# playa.net
KiCad netlist of a schematic drawn in EAGLE
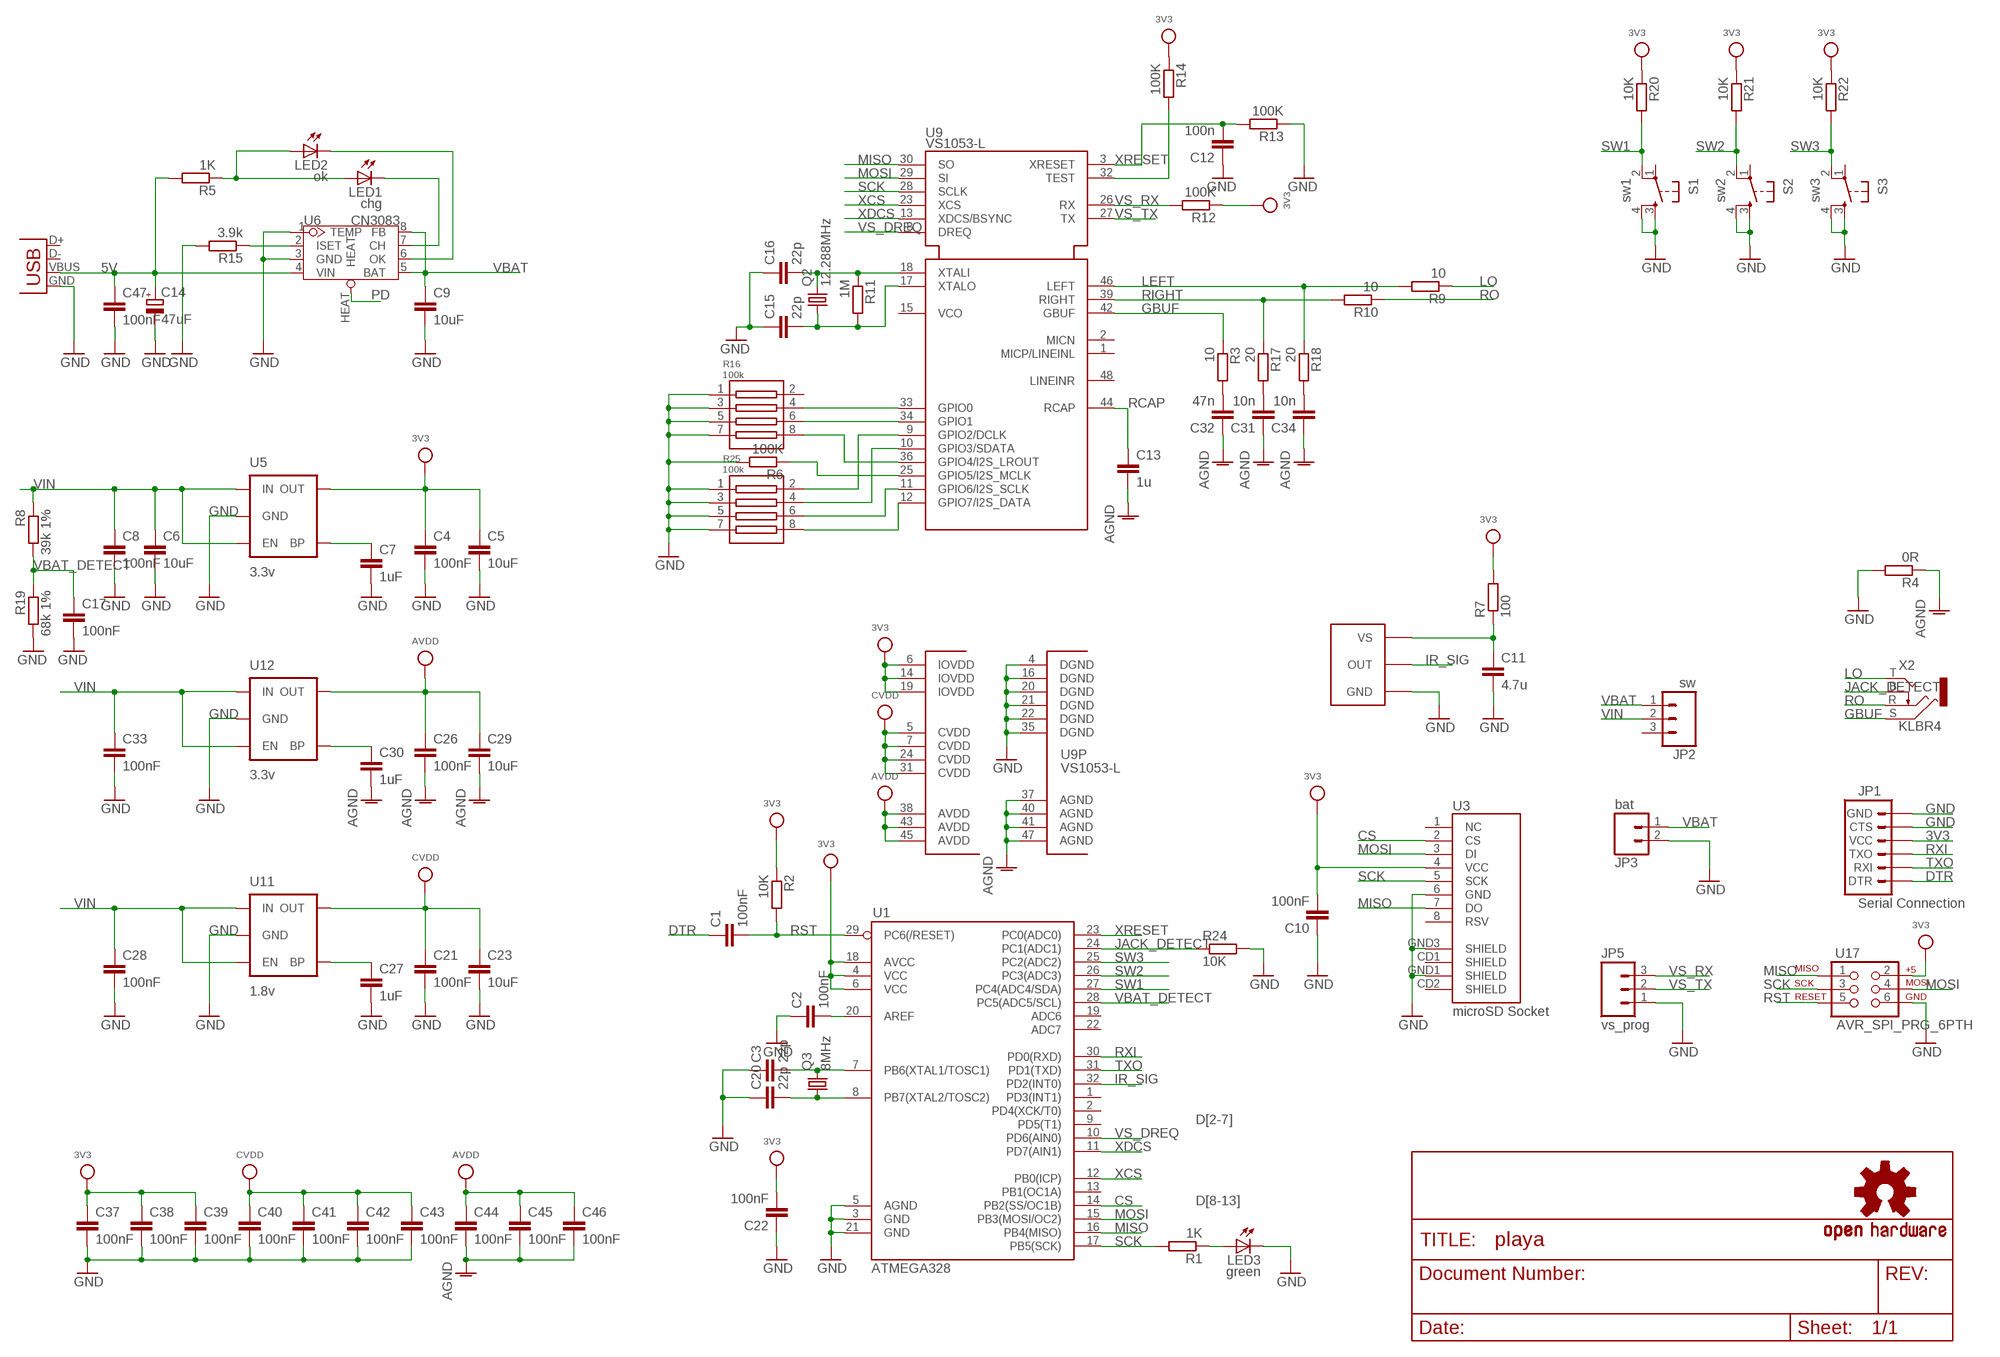
[diagram p0: schematic, sheet 1]

(export (version "E")
  (design (tool "Eeschema 10.0.6"))
  (components
    (comp (ref "C1")
      (value "100nF")
      (footprint "eagle-import:C0805")
      (libsource (lib "eagle-import") (part "C-EUC0805"))
    )
    (comp (ref "C2")
      (value "100nF")
      (footprint "eagle-import:C0805")
      (libsource (lib "eagle-import") (part "C-EUC0805"))
    )
    (comp (ref "C3")
      (value "22p")
      (footprint "eagle-import:C0805")
      (libsource (lib "eagle-import") (part "C-EUC0805"))
    )
    (comp (ref "C4")
      (value "100nF")
      (footprint "eagle-import:C0805")
      (libsource (lib "eagle-import") (part "C-EUC0805"))
    )
    (comp (ref "C5")
      (value "10uF")
      (footprint "eagle-import:C1206")
      (libsource (lib "eagle-import") (part "C-EUC1206"))
    )
    (comp (ref "C6")
      (value "10uF")
      (footprint "eagle-import:C1206")
      (libsource (lib "eagle-import") (part "C-EUC1206"))
    )
    (comp (ref "C7")
      (value "1uF")
      (footprint "eagle-import:C0805")
      (libsource (lib "eagle-import") (part "C-EUC0805"))
    )
    (comp (ref "C8")
      (value "100nF")
      (footprint "eagle-import:C0805")
      (libsource (lib "eagle-import") (part "C-EUC0805"))
    )
    (comp (ref "C9")
      (value "10uF")
      (footprint "eagle-import:C1206")
      (libsource (lib "eagle-import") (part "C-EUC1206"))
    )
    (comp (ref "C10")
      (value "100nF")
      (footprint "eagle-import:C0805")
      (libsource (lib "eagle-import") (part "C-EUC0805"))
    )
    (comp (ref "C11")
      (value "4.7u")
      (footprint "eagle-import:C1206")
      (libsource (lib "eagle-import") (part "C-EUC1206"))
    )
    (comp (ref "C12")
      (value "100n")
      (footprint "eagle-import:C0805")
      (libsource (lib "eagle-import") (part "C-EUC0805"))
    )
    (comp (ref "C13")
      (value "1u")
      (footprint "eagle-import:C0805")
      (libsource (lib "eagle-import") (part "C-EUC0805"))
    )
    (comp (ref "C14")
      (value "47uF")
      (footprint "eagle-import:CT7343")
      (libsource (lib "eagle-import") (part "CPOL-EUCT7343"))
    )
    (comp (ref "C15")
      (value "22p")
      (footprint "eagle-import:C0805")
      (libsource (lib "eagle-import") (part "C-EUC0805"))
    )
    (comp (ref "C16")
      (value "22p")
      (footprint "eagle-import:C0805")
      (libsource (lib "eagle-import") (part "C-EUC0805"))
    )
    (comp (ref "C17")
      (value "100nF")
      (footprint "eagle-import:C0805")
      (libsource (lib "eagle-import") (part "C-EUC0805"))
    )
    (comp (ref "C20")
      (value "22p")
      (footprint "eagle-import:C0805")
      (libsource (lib "eagle-import") (part "C-EUC0805"))
    )
    (comp (ref "C21")
      (value "100nF")
      (footprint "eagle-import:C0805")
      (libsource (lib "eagle-import") (part "C-EUC0805"))
    )
    (comp (ref "C22")
      (value "100nF")
      (footprint "eagle-import:C0805")
      (libsource (lib "eagle-import") (part "C-EUC0805"))
    )
    (comp (ref "C23")
      (value "10uF")
      (footprint "eagle-import:C1206")
      (libsource (lib "eagle-import") (part "C-EUC1206"))
    )
    (comp (ref "C26")
      (value "100nF")
      (footprint "eagle-import:C0805")
      (libsource (lib "eagle-import") (part "C-EUC0805"))
    )
    (comp (ref "C27")
      (value "1uF")
      (footprint "eagle-import:C0805")
      (libsource (lib "eagle-import") (part "C-EUC0805"))
    )
    (comp (ref "C28")
      (value "100nF")
      (footprint "eagle-import:C0805")
      (libsource (lib "eagle-import") (part "C-EUC0805"))
    )
    (comp (ref "C29")
      (value "10uF")
      (footprint "eagle-import:C1206")
      (libsource (lib "eagle-import") (part "C-EUC1206"))
    )
    (comp (ref "C30")
      (value "1uF")
      (footprint "eagle-import:C0805")
      (libsource (lib "eagle-import") (part "C-EUC0805"))
    )
    (comp (ref "C31")
      (value "10n")
      (footprint "eagle-import:C0805")
      (libsource (lib "eagle-import") (part "C-EUC0805"))
    )
    (comp (ref "C32")
      (value "47n")
      (footprint "eagle-import:C0805")
      (libsource (lib "eagle-import") (part "C-EUC0805"))
    )
    (comp (ref "C33")
      (value "100nF")
      (footprint "eagle-import:C0805")
      (libsource (lib "eagle-import") (part "C-EUC0805"))
    )
    (comp (ref "C34")
      (value "10n")
      (footprint "eagle-import:C0805")
      (libsource (lib "eagle-import") (part "C-EUC0805"))
    )
    (comp (ref "C37")
      (value "100nF")
      (footprint "eagle-import:C0805")
      (libsource (lib "eagle-import") (part "C-EUC0805"))
    )
    (comp (ref "C38")
      (value "100nF")
      (footprint "eagle-import:C0805")
      (libsource (lib "eagle-import") (part "C-EUC0805"))
    )
    (comp (ref "C39")
      (value "100nF")
      (footprint "eagle-import:C0805")
      (libsource (lib "eagle-import") (part "C-EUC0805"))
    )
    (comp (ref "C40")
      (value "100nF")
      (footprint "eagle-import:C0805")
      (libsource (lib "eagle-import") (part "C-EUC0805"))
    )
    (comp (ref "C41")
      (value "100nF")
      (footprint "eagle-import:C0805")
      (libsource (lib "eagle-import") (part "C-EUC0805"))
    )
    (comp (ref "C42")
      (value "100nF")
      (footprint "eagle-import:C0805")
      (libsource (lib "eagle-import") (part "C-EUC0805"))
    )
    (comp (ref "C43")
      (value "100nF")
      (footprint "eagle-import:C0805")
      (libsource (lib "eagle-import") (part "C-EUC0805"))
    )
    (comp (ref "C44")
      (value "100nF")
      (footprint "eagle-import:C0805")
      (libsource (lib "eagle-import") (part "C-EUC0805"))
    )
    (comp (ref "C45")
      (value "100nF")
      (footprint "eagle-import:C0805")
      (libsource (lib "eagle-import") (part "C-EUC0805"))
    )
    (comp (ref "C46")
      (value "100nF")
      (footprint "eagle-import:C0805")
      (libsource (lib "eagle-import") (part "C-EUC0805"))
    )
    (comp (ref "C47")
      (value "100nF")
      (footprint "eagle-import:C0805")
      (libsource (lib "eagle-import") (part "C-EUC0805"))
    )
    (comp (ref "JP1")
      (value "Serial Connection")
      (footprint "eagle-import:1X06")
      (libsource (lib "eagle-import") (part "ARDUINO_SERIAL_PROGRAMPTH"))
    )
    (comp (ref "JP2")
      (value "sw")
      (footprint "eagle-import:1X03")
      (libsource (lib "eagle-import") (part "M03PTH"))
    )
    (comp (ref "JP3")
      (value "bat")
      (footprint "eagle-import:1X02")
      (libsource (lib "eagle-import") (part "M02PTH"))
    )
    (comp (ref "JP5")
      (value "vs_prog")
      (footprint "eagle-import:1X03")
      (libsource (lib "eagle-import") (part "M03PTH"))
    )
    (comp (ref "LED1")
      (value "chg")
      (footprint "eagle-import:CHIP-LED0805")
      (libsource (lib "eagle-import") (part "LEDCHIP-LED0805"))
    )
    (comp (ref "LED2")
      (value "ok")
      (footprint "eagle-import:CHIP-LED0805")
      (libsource (lib "eagle-import") (part "LEDCHIP-LED0805"))
    )
    (comp (ref "LED3")
      (value "green")
      (footprint "eagle-import:CHIP-LED0805")
      (libsource (lib "eagle-import") (part "LEDCHIP-LED0805"))
    )
    (comp (ref "Q2")
      (value "12.288MHz")
      (footprint "eagle-import:CRYSTAL_5X3.2")
      (libsource (lib "eagle-import") (part "CRYTAL"))
    )
    (comp (ref "Q3")
      (value "8MHz")
      (footprint "eagle-import:CRYSTAL_5X3.2")
      (libsource (lib "eagle-import") (part "CRYTAL"))
    )
    (comp (ref "R1")
      (value "1K")
      (footprint "eagle-import:R0805W")
      (libsource (lib "eagle-import") (part "R-EU_R0805W"))
    )
    (comp (ref "R2")
      (value "10K")
      (footprint "eagle-import:R0805W")
      (libsource (lib "eagle-import") (part "R-EU_R0805W"))
    )
    (comp (ref "R3")
      (value "10")
      (footprint "eagle-import:R0805W")
      (libsource (lib "eagle-import") (part "R-EU_R0805W"))
    )
    (comp (ref "R4")
      (value "0R")
      (footprint "eagle-import:R0805W")
      (libsource (lib "eagle-import") (part "R-EU_R0805W"))
    )
    (comp (ref "R5")
      (value "1K")
      (footprint "eagle-import:R0805W")
      (libsource (lib "eagle-import") (part "R-EU_R0805W"))
    )
    (comp (ref "R6")
      (value "100K")
      (footprint "eagle-import:R0805W")
      (libsource (lib "eagle-import") (part "R-EU_R0805W"))
    )
    (comp (ref "R7")
      (value "100")
      (footprint "eagle-import:R0805W")
      (libsource (lib "eagle-import") (part "R-EU_R0805W"))
    )
    (comp (ref "R8")
      (value "39k 1%")
      (footprint "eagle-import:R0805W")
      (libsource (lib "eagle-import") (part "R-EU_R0805W"))
    )
    (comp (ref "R9")
      (value "10")
      (footprint "eagle-import:R0805W")
      (libsource (lib "eagle-import") (part "R-EU_R0805W"))
    )
    (comp (ref "R10")
      (value "10")
      (footprint "eagle-import:R0805W")
      (libsource (lib "eagle-import") (part "R-EU_R0805W"))
    )
    (comp (ref "R11")
      (value "1M")
      (footprint "eagle-import:R0805W")
      (libsource (lib "eagle-import") (part "R-EU_R0805W"))
    )
    (comp (ref "R12")
      (value "100K")
      (footprint "eagle-import:R0805W")
      (libsource (lib "eagle-import") (part "R-EU_R0805W"))
    )
    (comp (ref "R13")
      (value "100K")
      (footprint "eagle-import:R0805W")
      (libsource (lib "eagle-import") (part "R-EU_R0805W"))
    )
    (comp (ref "R14")
      (value "100K")
      (footprint "eagle-import:R0805W")
      (libsource (lib "eagle-import") (part "R-EU_R0805W"))
    )
    (comp (ref "R15")
      (value "3.9k")
      (footprint "eagle-import:R0805W")
      (libsource (lib "eagle-import") (part "R-EU_R0805W"))
    )
    (comp (ref "R16")
      (value "100k")
      (footprint "eagle-import:RAS_ARR_1206")
      (libsource (lib "eagle-import") (part "RES_ARR_1206"))
    )
    (comp (ref "R17")
      (value "20")
      (footprint "eagle-import:R0805W")
      (libsource (lib "eagle-import") (part "R-EU_R0805W"))
    )
    (comp (ref "R18")
      (value "20")
      (footprint "eagle-import:R0805W")
      (libsource (lib "eagle-import") (part "R-EU_R0805W"))
    )
    (comp (ref "R19")
      (value "68k 1%")
      (footprint "eagle-import:R0805W")
      (libsource (lib "eagle-import") (part "R-EU_R0805W"))
    )
    (comp (ref "R20")
      (value "10K")
      (footprint "eagle-import:R0805W")
      (libsource (lib "eagle-import") (part "R-EU_R0805W"))
    )
    (comp (ref "R21")
      (value "10K")
      (footprint "eagle-import:R0805W")
      (libsource (lib "eagle-import") (part "R-EU_R0805W"))
    )
    (comp (ref "R22")
      (value "10K")
      (footprint "eagle-import:R0805W")
      (libsource (lib "eagle-import") (part "R-EU_R0805W"))
    )
    (comp (ref "R24")
      (value "10K")
      (footprint "eagle-import:R0805W")
      (libsource (lib "eagle-import") (part "R-EU_R0805W"))
    )
    (comp (ref "R25")
      (value "100k")
      (footprint "eagle-import:RAS_ARR_1206")
      (libsource (lib "eagle-import") (part "RES_ARR_1206"))
    )
    (comp (ref "S1")
      (value "sw1")
      (footprint "eagle-import:TACTILE_SWITCH_SMD")
      (libsource (lib "eagle-import") (part "TAC_SWITCHSMD"))
    )
    (comp (ref "S2")
      (value "sw2")
      (footprint "eagle-import:TACTILE_SWITCH_SMD")
      (libsource (lib "eagle-import") (part "TAC_SWITCHSMD"))
    )
    (comp (ref "S3")
      (value "sw3")
      (footprint "eagle-import:TACTILE_SWITCH_SMD")
      (libsource (lib "eagle-import") (part "TAC_SWITCHSMD"))
    )
    (comp (ref "U$3")
      (value "TSOP312X")
      (footprint "eagle-import:TSOP312X")
      (libsource (lib "eagle-import") (part "TSOP312X"))
    )
    (comp (ref "U$5")
      (value "OSHW-LOGOM")
      (footprint "eagle-import:OSHW-LOGO-M")
      (libsource (lib "eagle-import") (part "OSHW-LOGOM"))
    )
    (comp (ref "U1")
      (value "ATMEGA328")
      (footprint "eagle-import:TQFP32-08")
      (libsource (lib "eagle-import") (part "ATMEGA168"))
    )
    (comp (ref "U3")
      (value "microSD Socket")
      (footprint "eagle-import:MICRO-SD-SOCKET-PP")
      (libsource (lib "eagle-import") (part "USD-SOCKETNEW"))
    )
    (comp (ref "U5")
      (value "3.3v")
      (footprint "eagle-import:SOT23-5")
      (libsource (lib "eagle-import") (part "V_REG_LDOSMD"))
    )
    (comp (ref "U6")
      (value "CN3083")
      (footprint "eagle-import:SOP8-W_-HEAT")
      (libsource (lib "eagle-import") (part "CN3083"))
    )
    (comp (ref "U9")
      (value "VS1053-L")
      (footprint "eagle-import:LQFP48")
      (libsource (lib "eagle-import") (part "VS1053-L"))
    )
    (comp (ref "U11")
      (value "1.8v")
      (footprint "eagle-import:SOT23-5")
      (libsource (lib "eagle-import") (part "V_REG_LDOSMD"))
    )
    (comp (ref "U12")
      (value "3.3v")
      (footprint "eagle-import:SOT23-5")
      (libsource (lib "eagle-import") (part "V_REG_LDOSMD"))
    )
    (comp (ref "U17")
      (value "AVR_SPI_PRG_6PTH")
      (footprint "eagle-import:2X3")
      (libsource (lib "eagle-import") (part "AVR_SPI_PRG_6PTH"))
    )
    (comp (ref "X1")
      (value "USBSMD")
      (footprint "eagle-import:USB-MINIB")
      (libsource (lib "eagle-import") (part "USBSMD"))
    )
    (comp (ref "X2")
      (value "KLBR4")
      (footprint "eagle-import:KLBR4")
      (fields (field (name "MPN") "KLBR 4"))
      (libsource (lib "eagle-import") (part "KLBR4"))
    )
  )
  (nets
    (net (code "1") (name "/5V") (class "Default")
      (node (ref "C14") (pin "+") (pinfunction "+_+") (pintype "passive"))
      (node (ref "C47") (pin "1") (pinfunction "1_1") (pintype "passive"))
      (node (ref "R5") (pin "2") (pinfunction "2_2") (pintype "passive"))
      (node (ref "U6") (pin "4") (pinfunction "VIN_4") (pintype "bidirectional"))
      (node (ref "X1") (pin "VBUS") (pinfunction "VBUS_VBUS") (pintype "bidirectional"))
    )
    (net (code "2") (name "/CS") (class "Default")
      (node (ref "U1") (pin "14") (pinfunction "PB2(SS/OC1B)_14") (pintype "bidirectional"))
      (node (ref "U3") (pin "2") (pinfunction "CS_2") (pintype "bidirectional"))
    )
    (net (code "3") (name "/DTR") (class "Default")
      (node (ref "C1") (pin "1") (pinfunction "1_1") (pintype "passive"))
      (node (ref "JP1") (pin "1") (pinfunction "DTR_1") (pintype "passive"))
    )
    (net (code "4") (name "/GBUF") (class "Default")
      (node (ref "R3") (pin "1") (pinfunction "1_1") (pintype "passive"))
      (node (ref "U9") (pin "42") (pinfunction "GBUF_42") (pintype "output"))
      (node (ref "X2") (pin "S") (pinfunction "S_S") (pintype "passive"))
    )
    (net (code "5") (name "/IR_SIG") (class "Default")
      (node (ref "U$3") (pin "3") (pinfunction "OUT_3") (pintype "bidirectional"))
      (node (ref "U1") (pin "32") (pinfunction "PD2(INT0)_32") (pintype "bidirectional"))
    )
    (net (code "6") (name "/JACK_DETECT") (class "Default")
      (node (ref "R24") (pin "1") (pinfunction "1_1") (pintype "passive"))
      (node (ref "U1") (pin "24") (pinfunction "PC1(ADC1)_24") (pintype "bidirectional"))
      (node (ref "X2") (pin "B") (pinfunction "B_B") (pintype "passive"))
    )
    (net (code "7") (name "/LEFT") (class "Default")
      (node (ref "R18") (pin "1") (pinfunction "1_1") (pintype "passive"))
      (node (ref "R9") (pin "2") (pinfunction "2_2") (pintype "passive"))
      (node (ref "U9") (pin "46") (pinfunction "LEFT_46") (pintype "output"))
    )
    (net (code "8") (name "/LO") (class "Default")
      (node (ref "R9") (pin "1") (pinfunction "1_1") (pintype "passive"))
      (node (ref "X2") (pin "T") (pinfunction "T_T") (pintype "passive"))
    )
    (net (code "9") (name "/MISO") (class "Default")
      (node (ref "U1") (pin "16") (pinfunction "PB4(MISO)_16") (pintype "bidirectional"))
      (node (ref "U17") (pin "1") (pinfunction "1_1") (pintype "passive"))
      (node (ref "U3") (pin "7") (pinfunction "DO_7") (pintype "bidirectional"))
      (node (ref "U9") (pin "30") (pinfunction "SO_30") (pintype "output"))
    )
    (net (code "10") (name "/MOSI") (class "Default")
      (node (ref "U1") (pin "15") (pinfunction "PB3(MOSI/OC2)_15") (pintype "bidirectional"))
      (node (ref "U17") (pin "4") (pinfunction "4_4") (pintype "passive"))
      (node (ref "U3") (pin "3") (pinfunction "DI_3") (pintype "bidirectional"))
      (node (ref "U9") (pin "29") (pinfunction "SI_29") (pintype "input"))
    )
    (net (code "11") (name "/PD") (class "Default")
      (node (ref "U6") (pin "HEAT") (pinfunction "HEAT_HEAT") (pintype "bidirectional"))
    )
    (net (code "12") (name "/RCAP") (class "Default")
      (node (ref "C13") (pin "1") (pinfunction "1_1") (pintype "passive"))
      (node (ref "U9") (pin "44") (pinfunction "RCAP_44") (pintype "bidirectional"))
    )
    (net (code "13") (name "/RIGHT") (class "Default")
      (node (ref "R10") (pin "2") (pinfunction "2_2") (pintype "passive"))
      (node (ref "R17") (pin "1") (pinfunction "1_1") (pintype "passive"))
      (node (ref "U9") (pin "39") (pinfunction "RIGHT_39") (pintype "output"))
    )
    (net (code "14") (name "/RO") (class "Default")
      (node (ref "R10") (pin "1") (pinfunction "1_1") (pintype "passive"))
      (node (ref "X2") (pin "R") (pinfunction "R_R") (pintype "passive"))
    )
    (net (code "15") (name "/RST") (class "Default")
      (node (ref "C1") (pin "2") (pinfunction "2_2") (pintype "passive"))
      (node (ref "R2") (pin "2") (pinfunction "2_2") (pintype "passive"))
      (node (ref "U1") (pin "29") (pinfunction "PC6(/RESET)_29") (pintype "bidirectional"))
      (node (ref "U17") (pin "5") (pinfunction "5_5") (pintype "passive"))
    )
    (net (code "16") (name "/RXI") (class "Default")
      (node (ref "JP1") (pin "3") (pinfunction "TXO_3") (pintype "passive"))
      (node (ref "U1") (pin "30") (pinfunction "PD0(RXD)_30") (pintype "bidirectional"))
    )
    (net (code "17") (name "/SCK") (class "Default")
      (node (ref "R1") (pin "2") (pinfunction "2_2") (pintype "passive"))
      (node (ref "U1") (pin "17") (pinfunction "PB5(SCK)_17") (pintype "bidirectional"))
      (node (ref "U17") (pin "3") (pinfunction "3_3") (pintype "passive"))
      (node (ref "U3") (pin "5") (pinfunction "SCK_5") (pintype "bidirectional"))
      (node (ref "U9") (pin "28") (pinfunction "SCLK_28") (pintype "input"))
    )
    (net (code "18") (name "/SW1") (class "Default")
      (node (ref "R20") (pin "2") (pinfunction "2_2") (pintype "passive"))
      (node (ref "S1") (pin "2") (pinfunction "2_2") (pintype "passive"))
      (node (ref "U1") (pin "27") (pinfunction "PC4(ADC4/SDA)_27") (pintype "bidirectional"))
    )
    (net (code "19") (name "/SW2") (class "Default")
      (node (ref "R21") (pin "2") (pinfunction "2_2") (pintype "passive"))
      (node (ref "S2") (pin "2") (pinfunction "2_2") (pintype "passive"))
      (node (ref "U1") (pin "26") (pinfunction "PC3(ADC3)_26") (pintype "bidirectional"))
    )
    (net (code "20") (name "/SW3") (class "Default")
      (node (ref "R22") (pin "2") (pinfunction "2_2") (pintype "passive"))
      (node (ref "S3") (pin "2") (pinfunction "2_2") (pintype "passive"))
      (node (ref "U1") (pin "25") (pinfunction "PC2(ADC2)_25") (pintype "bidirectional"))
    )
    (net (code "21") (name "/TXO") (class "Default")
      (node (ref "JP1") (pin "2") (pinfunction "RXI_2") (pintype "passive"))
      (node (ref "U1") (pin "31") (pinfunction "PD1(TXD)_31") (pintype "bidirectional"))
    )
    (net (code "22") (name "/VBAT") (class "Default")
      (node (ref "C9") (pin "1") (pinfunction "1_1") (pintype "passive"))
      (node (ref "JP2") (pin "1") (pinfunction "1_1") (pintype "passive"))
      (node (ref "JP3") (pin "1") (pinfunction "1_1") (pintype "passive"))
      (node (ref "U6") (pin "5") (pinfunction "BAT_5") (pintype "bidirectional"))
      (node (ref "U6") (pin "8") (pinfunction "FB_8") (pintype "bidirectional"))
    )
    (net (code "23") (name "/VBAT_DETECT") (class "Default")
      (node (ref "C17") (pin "1") (pinfunction "1_1") (pintype "passive"))
      (node (ref "R19") (pin "1") (pinfunction "1_1") (pintype "passive"))
      (node (ref "R8") (pin "2") (pinfunction "2_2") (pintype "passive"))
      (node (ref "U1") (pin "28") (pinfunction "PC5(ADC5/SCL)_28") (pintype "bidirectional"))
    )
    (net (code "24") (name "/VIN") (class "Default")
      (node (ref "C28") (pin "1") (pinfunction "1_1") (pintype "passive"))
      (node (ref "C33") (pin "1") (pinfunction "1_1") (pintype "passive"))
      (node (ref "C6") (pin "1") (pinfunction "1_1") (pintype "passive"))
      (node (ref "C8") (pin "1") (pinfunction "1_1") (pintype "passive"))
      (node (ref "JP2") (pin "2") (pinfunction "2_2") (pintype "passive"))
      (node (ref "R8") (pin "1") (pinfunction "1_1") (pintype "passive"))
      (node (ref "U11") (pin "1") (pinfunction "IN_1") (pintype "input"))
      (node (ref "U11") (pin "3") (pinfunction "EN_3") (pintype "input"))
      (node (ref "U12") (pin "1") (pinfunction "IN_1") (pintype "input"))
      (node (ref "U12") (pin "3") (pinfunction "EN_3") (pintype "input"))
      (node (ref "U5") (pin "1") (pinfunction "IN_1") (pintype "input"))
      (node (ref "U5") (pin "3") (pinfunction "EN_3") (pintype "input"))
    )
    (net (code "25") (name "/VS_DREQ") (class "Default")
      (node (ref "U1") (pin "10") (pinfunction "PD6(AIN0)_10") (pintype "bidirectional"))
      (node (ref "U9") (pin "8") (pinfunction "DREQ_8") (pintype "output"))
    )
    (net (code "26") (name "/VS_RX") (class "Default")
      (node (ref "JP5") (pin "3") (pinfunction "3_3") (pintype "passive"))
      (node (ref "R12") (pin "2") (pinfunction "2_2") (pintype "passive"))
      (node (ref "U9") (pin "26") (pinfunction "RX_26") (pintype "input"))
    )
    (net (code "27") (name "/VS_TX") (class "Default")
      (node (ref "JP5") (pin "2") (pinfunction "2_2") (pintype "passive"))
      (node (ref "U9") (pin "27") (pinfunction "TX_27") (pintype "output"))
    )
    (net (code "28") (name "/XCS") (class "Default")
      (node (ref "U1") (pin "12") (pinfunction "PB0(ICP)_12") (pintype "bidirectional"))
      (node (ref "U9") (pin "23") (pinfunction "XCS_23") (pintype "input"))
    )
    (net (code "29") (name "/XDCS") (class "Default")
      (node (ref "U1") (pin "11") (pinfunction "PD7(AIN1)_11") (pintype "bidirectional"))
      (node (ref "U9") (pin "13") (pinfunction "XDCS/BSYNC_13") (pintype "input"))
    )
    (net (code "30") (name "/XRESET") (class "Default")
      (node (ref "C12") (pin "2") (pinfunction "2_2") (pintype "passive"))
      (node (ref "R13") (pin "2") (pinfunction "2_2") (pintype "passive"))
      (node (ref "U1") (pin "23") (pinfunction "PC0(ADC0)_23") (pintype "bidirectional"))
      (node (ref "U9") (pin "3") (pinfunction "XRESET_3") (pintype "input"))
    )
    (net (code "31") (name "3V3") (class "Default")
      (node (ref "C10") (pin "2") (pinfunction "2_2") (pintype "passive"))
      (node (ref "C22") (pin "2") (pinfunction "2_2") (pintype "passive"))
      (node (ref "C37") (pin "1") (pinfunction "1_1") (pintype "passive"))
      (node (ref "C38") (pin "1") (pinfunction "1_1") (pintype "passive"))
      (node (ref "C39") (pin "1") (pinfunction "1_1") (pintype "passive"))
      (node (ref "C4") (pin "1") (pinfunction "1_1") (pintype "passive"))
      (node (ref "C5") (pin "1") (pinfunction "1_1") (pintype "passive"))
      (node (ref "JP1") (pin "4") (pinfunction "VCC_4") (pintype "passive"))
      (node (ref "R12") (pin "1") (pinfunction "1_1") (pintype "passive"))
      (node (ref "R14") (pin "1") (pinfunction "1_1") (pintype "passive"))
      (node (ref "R2") (pin "1") (pinfunction "1_1") (pintype "passive"))
      (node (ref "R20") (pin "1") (pinfunction "1_1") (pintype "passive"))
      (node (ref "R21") (pin "1") (pinfunction "1_1") (pintype "passive"))
      (node (ref "R22") (pin "1") (pinfunction "1_1") (pintype "passive"))
      (node (ref "R7") (pin "2") (pinfunction "2_2") (pintype "passive"))
      (node (ref "U1") (pin "18") (pinfunction "AVCC_18") (pintype "bidirectional"))
      (node (ref "U1") (pin "4") (pinfunction "VCC_4") (pintype "bidirectional"))
      (node (ref "U1") (pin "6") (pinfunction "VCC_6") (pintype "bidirectional"))
      (node (ref "U17") (pin "2") (pinfunction "2_2") (pintype "passive"))
      (node (ref "U3") (pin "4") (pinfunction "VCC_4") (pintype "bidirectional"))
      (node (ref "U5") (pin "5") (pinfunction "OUT_5") (pintype "passive"))
      (node (ref "U9") (pin "14") (pinfunction "IOVDD_14") (pintype "power_in"))
      (node (ref "U9") (pin "19") (pinfunction "IOVDD_19") (pintype "power_in"))
      (node (ref "U9") (pin "6") (pinfunction "IOVDD_6") (pintype "power_in"))
    )
    (net (code "32") (name "AGND") (class "Default")
      (node (ref "C13") (pin "2") (pinfunction "2_2") (pintype "passive"))
      (node (ref "C26") (pin "2") (pinfunction "2_2") (pintype "passive"))
      (node (ref "C29") (pin "2") (pinfunction "2_2") (pintype "passive"))
      (node (ref "C30") (pin "2") (pinfunction "2_2") (pintype "passive"))
      (node (ref "C31") (pin "1") (pinfunction "1_1") (pintype "passive"))
      (node (ref "C32") (pin "1") (pinfunction "1_1") (pintype "passive"))
      (node (ref "C34") (pin "1") (pinfunction "1_1") (pintype "passive"))
      (node (ref "C44") (pin "2") (pinfunction "2_2") (pintype "passive"))
      (node (ref "C45") (pin "2") (pinfunction "2_2") (pintype "passive"))
      (node (ref "C46") (pin "2") (pinfunction "2_2") (pintype "passive"))
      (node (ref "R4") (pin "1") (pinfunction "1_1") (pintype "passive"))
      (node (ref "U9") (pin "37") (pinfunction "AGND_37") (pintype "power_in"))
      (node (ref "U9") (pin "40") (pinfunction "AGND_40") (pintype "power_in"))
      (node (ref "U9") (pin "41") (pinfunction "AGND_41") (pintype "power_in"))
      (node (ref "U9") (pin "47") (pinfunction "AGND_47") (pintype "power_in"))
    )
    (net (code "33") (name "AVDD") (class "Default")
      (node (ref "C26") (pin "1") (pinfunction "1_1") (pintype "passive"))
      (node (ref "C29") (pin "1") (pinfunction "1_1") (pintype "passive"))
      (node (ref "C44") (pin "1") (pinfunction "1_1") (pintype "passive"))
      (node (ref "C45") (pin "1") (pinfunction "1_1") (pintype "passive"))
      (node (ref "C46") (pin "1") (pinfunction "1_1") (pintype "passive"))
      (node (ref "U12") (pin "5") (pinfunction "OUT_5") (pintype "passive"))
      (node (ref "U9") (pin "38") (pinfunction "AVDD_38") (pintype "power_in"))
      (node (ref "U9") (pin "43") (pinfunction "AVDD_43") (pintype "power_in"))
      (node (ref "U9") (pin "45") (pinfunction "AVDD_45") (pintype "power_in"))
    )
    (net (code "34") (name "CVDD") (class "Default")
      (node (ref "C21") (pin "1") (pinfunction "1_1") (pintype "passive"))
      (node (ref "C23") (pin "1") (pinfunction "1_1") (pintype "passive"))
      (node (ref "C40") (pin "1") (pinfunction "1_1") (pintype "passive"))
      (node (ref "C41") (pin "1") (pinfunction "1_1") (pintype "passive"))
      (node (ref "C42") (pin "1") (pinfunction "1_1") (pintype "passive"))
      (node (ref "C43") (pin "1") (pinfunction "1_1") (pintype "passive"))
      (node (ref "U11") (pin "5") (pinfunction "OUT_5") (pintype "passive"))
      (node (ref "U9") (pin "24") (pinfunction "CVDD_24") (pintype "power_in"))
      (node (ref "U9") (pin "31") (pinfunction "CVDD_31") (pintype "power_in"))
      (node (ref "U9") (pin "5") (pinfunction "CVDD_5") (pintype "power_in"))
      (node (ref "U9") (pin "7") (pinfunction "CVDD_7") (pintype "power_in"))
    )
    (net (code "35") (name "GND") (class "Default")
      (node (ref "C10") (pin "1") (pinfunction "1_1") (pintype "passive"))
      (node (ref "C11") (pin "2") (pinfunction "2_2") (pintype "passive"))
      (node (ref "C12") (pin "1") (pinfunction "1_1") (pintype "passive"))
      (node (ref "C14") (pin "-") (pinfunction "-_-") (pintype "passive"))
      (node (ref "C15") (pin "1") (pinfunction "1_1") (pintype "passive"))
      (node (ref "C16") (pin "1") (pinfunction "1_1") (pintype "passive"))
      (node (ref "C17") (pin "2") (pinfunction "2_2") (pintype "passive"))
      (node (ref "C2") (pin "1") (pinfunction "1_1") (pintype "passive"))
      (node (ref "C20") (pin "1") (pinfunction "1_1") (pintype "passive"))
      (node (ref "C21") (pin "2") (pinfunction "2_2") (pintype "passive"))
      (node (ref "C22") (pin "1") (pinfunction "1_1") (pintype "passive"))
      (node (ref "C23") (pin "2") (pinfunction "2_2") (pintype "passive"))
      (node (ref "C27") (pin "2") (pinfunction "2_2") (pintype "passive"))
      (node (ref "C28") (pin "2") (pinfunction "2_2") (pintype "passive"))
      (node (ref "C3") (pin "1") (pinfunction "1_1") (pintype "passive"))
      (node (ref "C33") (pin "2") (pinfunction "2_2") (pintype "passive"))
      (node (ref "C37") (pin "2") (pinfunction "2_2") (pintype "passive"))
      (node (ref "C38") (pin "2") (pinfunction "2_2") (pintype "passive"))
      (node (ref "C39") (pin "2") (pinfunction "2_2") (pintype "passive"))
      (node (ref "C4") (pin "2") (pinfunction "2_2") (pintype "passive"))
      (node (ref "C40") (pin "2") (pinfunction "2_2") (pintype "passive"))
      (node (ref "C41") (pin "2") (pinfunction "2_2") (pintype "passive"))
      (node (ref "C42") (pin "2") (pinfunction "2_2") (pintype "passive"))
      (node (ref "C43") (pin "2") (pinfunction "2_2") (pintype "passive"))
      (node (ref "C47") (pin "2") (pinfunction "2_2") (pintype "passive"))
      (node (ref "C5") (pin "2") (pinfunction "2_2") (pintype "passive"))
      (node (ref "C6") (pin "2") (pinfunction "2_2") (pintype "passive"))
      (node (ref "C7") (pin "2") (pinfunction "2_2") (pintype "passive"))
      (node (ref "C8") (pin "2") (pinfunction "2_2") (pintype "passive"))
      (node (ref "C9") (pin "2") (pinfunction "2_2") (pintype "passive"))
      (node (ref "JP1") (pin "5") (pinfunction "CTS_5") (pintype "passive"))
      (node (ref "JP1") (pin "6") (pinfunction "GND_6") (pintype "passive"))
      (node (ref "JP3") (pin "2") (pinfunction "2_2") (pintype "passive"))
      (node (ref "JP5") (pin "1") (pinfunction "1_1") (pintype "passive"))
      (node (ref "LED3") (pin "C") (pinfunction "C_C") (pintype "passive"))
      (node (ref "R13") (pin "1") (pinfunction "1_1") (pintype "passive"))
      (node (ref "R15") (pin "2") (pinfunction "2_2") (pintype "passive"))
      (node (ref "R16") (pin "1") (pinfunction "1_1") (pintype "passive"))
      (node (ref "R16") (pin "3") (pinfunction "3_3") (pintype "passive"))
      (node (ref "R16") (pin "5") (pinfunction "5_5") (pintype "passive"))
      (node (ref "R16") (pin "7") (pinfunction "7_7") (pintype "passive"))
      (node (ref "R19") (pin "2") (pinfunction "2_2") (pintype "passive"))
      (node (ref "R24") (pin "2") (pinfunction "2_2") (pintype "passive"))
      (node (ref "R25") (pin "1") (pinfunction "1_1") (pintype "passive"))
      (node (ref "R25") (pin "3") (pinfunction "3_3") (pintype "passive"))
      (node (ref "R25") (pin "5") (pinfunction "5_5") (pintype "passive"))
      (node (ref "R25") (pin "7") (pinfunction "7_7") (pintype "passive"))
      (node (ref "R4") (pin "2") (pinfunction "2_2") (pintype "passive"))
      (node (ref "R6") (pin "2") (pinfunction "2_2") (pintype "passive"))
      (node (ref "S1") (pin "3") (pinfunction "3_3") (pintype "passive"))
      (node (ref "S1") (pin "4") (pinfunction "4_4") (pintype "passive"))
      (node (ref "S2") (pin "3") (pinfunction "3_3") (pintype "passive"))
      (node (ref "S2") (pin "4") (pinfunction "4_4") (pintype "passive"))
      (node (ref "S3") (pin "3") (pinfunction "3_3") (pintype "passive"))
      (node (ref "S3") (pin "4") (pinfunction "4_4") (pintype "passive"))
      (node (ref "U$3") (pin "1") (pinfunction "GND_1") (pintype "bidirectional"))
      (node (ref "U1") (pin "21") (pinfunction "GND_21") (pintype "bidirectional"))
      (node (ref "U1") (pin "3") (pinfunction "GND_3") (pintype "bidirectional"))
      (node (ref "U1") (pin "5") (pinfunction "AGND_5") (pintype "bidirectional"))
      (node (ref "U11") (pin "2") (pinfunction "GND_2") (pintype "input"))
      (node (ref "U12") (pin "2") (pinfunction "GND_2") (pintype "input"))
      (node (ref "U17") (pin "6") (pinfunction "6_6") (pintype "passive"))
      (node (ref "U3") (pin "6") (pinfunction "GND_6") (pintype "bidirectional"))
      (node (ref "U3") (pin "GND1") (pinfunction "SHIELD_GND1") (pintype "bidirectional"))
      (node (ref "U3") (pin "GND3") (pinfunction "SHIELD_GND3") (pintype "bidirectional"))
      (node (ref "U5") (pin "2") (pinfunction "GND_2") (pintype "input"))
      (node (ref "U6") (pin "1") (pinfunction "TEMP_1") (pintype "bidirectional"))
      (node (ref "U6") (pin "3") (pinfunction "GND_3") (pintype "bidirectional"))
      (node (ref "U9") (pin "16") (pinfunction "DGND_16") (pintype "power_in"))
      (node (ref "U9") (pin "20") (pinfunction "DGND_20") (pintype "power_in"))
      (node (ref "U9") (pin "21") (pinfunction "DGND_21") (pintype "power_in"))
      (node (ref "U9") (pin "22") (pinfunction "DGND_22") (pintype "power_in"))
      (node (ref "U9") (pin "35") (pinfunction "DGND_35") (pintype "power_in"))
      (node (ref "U9") (pin "4") (pinfunction "DGND_4") (pintype "power_in"))
      (node (ref "X1") (pin "GND") (pinfunction "GND_GND") (pintype "bidirectional"))
    )
    (net (code "36") (name "Net-(C31-Pad2)") (class "Default")
      (node (ref "C31") (pin "2") (pinfunction "2_2") (pintype "passive"))
      (node (ref "R17") (pin "2") (pinfunction "2_2") (pintype "passive"))
    )
    (net (code "37") (name "Net-(C32-Pad2)") (class "Default")
      (node (ref "C32") (pin "2") (pinfunction "2_2") (pintype "passive"))
      (node (ref "R3") (pin "2") (pinfunction "2_2") (pintype "passive"))
    )
    (net (code "38") (name "Net-(C34-Pad2)") (class "Default")
      (node (ref "C34") (pin "2") (pinfunction "2_2") (pintype "passive"))
      (node (ref "R18") (pin "2") (pinfunction "2_2") (pintype "passive"))
    )
    (net (code "39") (name "Net-(LED1-PadA)") (class "Default")
      (node (ref "LED1") (pin "A") (pinfunction "A_A") (pintype "passive"))
      (node (ref "LED2") (pin "A") (pinfunction "A_A") (pintype "passive"))
      (node (ref "R5") (pin "1") (pinfunction "1_1") (pintype "passive"))
    )
    (net (code "40") (name "Net-(LED3-PadA)") (class "Default")
      (node (ref "LED3") (pin "A") (pinfunction "A_A") (pintype "passive"))
      (node (ref "R1") (pin "1") (pinfunction "1_1") (pintype "passive"))
    )
    (net (code "41") (name "Net-(Q2-1)") (class "Default")
      (node (ref "C15") (pin "2") (pinfunction "2_2") (pintype "passive"))
      (node (ref "Q2") (pin "P$1") (pinfunction "1_P$1") (pintype "passive"))
      (node (ref "R11") (pin "2") (pinfunction "2_2") (pintype "passive"))
      (node (ref "U9") (pin "17") (pinfunction "XTALO_17") (pintype "output"))
    )
    (net (code "42") (name "Net-(Q2-2)") (class "Default")
      (node (ref "C16") (pin "2") (pinfunction "2_2") (pintype "passive"))
      (node (ref "Q2") (pin "P$2") (pinfunction "2_P$2") (pintype "passive"))
      (node (ref "R11") (pin "1") (pinfunction "1_1") (pintype "passive"))
      (node (ref "U9") (pin "18") (pinfunction "XTALI_18") (pintype "input"))
    )
    (net (code "43") (name "Net-(Q3-1)") (class "Default")
      (node (ref "C20") (pin "2") (pinfunction "2_2") (pintype "passive"))
      (node (ref "Q3") (pin "P$1") (pinfunction "1_P$1") (pintype "passive"))
      (node (ref "U1") (pin "8") (pinfunction "PB7(XTAL2/TOSC2)_8") (pintype "bidirectional"))
    )
    (net (code "44") (name "Net-(Q3-2)") (class "Default")
      (node (ref "C3") (pin "2") (pinfunction "2_2") (pintype "passive"))
      (node (ref "Q3") (pin "P$2") (pinfunction "2_P$2") (pintype "passive"))
      (node (ref "U1") (pin "7") (pinfunction "PB6(XTAL1/TOSC1)_7") (pintype "bidirectional"))
    )
    (net (code "45") (name "Net-(U$3-VS)") (class "Default")
      (node (ref "C11") (pin "1") (pinfunction "1_1") (pintype "passive"))
      (node (ref "R7") (pin "1") (pinfunction "1_1") (pintype "passive"))
      (node (ref "U$3") (pin "2") (pinfunction "VS_2") (pintype "bidirectional"))
    )
    (net (code "46") (name "Net-(U1-AREF)") (class "Default")
      (node (ref "C2") (pin "2") (pinfunction "2_2") (pintype "passive"))
      (node (ref "U1") (pin "20") (pinfunction "AREF_20") (pintype "bidirectional"))
    )
    (net (code "47") (name "Net-(U5-BP)") (class "Default")
      (node (ref "C7") (pin "1") (pinfunction "1_1") (pintype "passive"))
      (node (ref "U5") (pin "4") (pinfunction "BP_4") (pintype "input"))
    )
    (net (code "48") (name "Net-(U6-CH)") (class "Default")
      (node (ref "LED1") (pin "C") (pinfunction "C_C") (pintype "passive"))
      (node (ref "U6") (pin "7") (pinfunction "CH_7") (pintype "bidirectional"))
    )
    (net (code "49") (name "Net-(U6-ISET)") (class "Default")
      (node (ref "R15") (pin "1") (pinfunction "1_1") (pintype "passive"))
      (node (ref "U6") (pin "2") (pinfunction "ISET_2") (pintype "bidirectional"))
    )
    (net (code "50") (name "Net-(U6-OK)") (class "Default")
      (node (ref "LED2") (pin "C") (pinfunction "C_C") (pintype "passive"))
      (node (ref "U6") (pin "6") (pinfunction "OK_6") (pintype "bidirectional"))
    )
    (net (code "51") (name "Net-(U9A-GPIO0)") (class "Default")
      (node (ref "R16") (pin "4") (pinfunction "4_4") (pintype "passive"))
      (node (ref "U9") (pin "33") (pinfunction "GPIO0_33") (pintype "bidirectional"))
    )
    (net (code "52") (name "Net-(U9A-GPIO1)") (class "Default")
      (node (ref "R16") (pin "6") (pinfunction "6_6") (pintype "passive"))
      (node (ref "U9") (pin "34") (pinfunction "GPIO1_34") (pintype "bidirectional"))
    )
    (net (code "53") (name "Net-(U9A-GPIO2{slash}DCLK)") (class "Default")
      (node (ref "R25") (pin "2") (pinfunction "2_2") (pintype "passive"))
      (node (ref "U9") (pin "9") (pinfunction "GPIO2/DCLK_9") (pintype "bidirectional"))
    )
    (net (code "54") (name "Net-(U9A-GPIO3{slash}SDATA)") (class "Default")
      (node (ref "R25") (pin "4") (pinfunction "4_4") (pintype "passive"))
      (node (ref "U9") (pin "10") (pinfunction "GPIO3/SDATA_10") (pintype "bidirectional"))
    )
    (net (code "55") (name "Net-(U9A-GPIO4{slash}I2S_LROUT)") (class "Default")
      (node (ref "R16") (pin "8") (pinfunction "8_8") (pintype "passive"))
      (node (ref "U9") (pin "36") (pinfunction "GPIO4/I2S_LROUT_36") (pintype "bidirectional"))
    )
    (net (code "56") (name "Net-(U9A-GPIO5{slash}I2S_MCLK)") (class "Default")
      (node (ref "R6") (pin "1") (pinfunction "1_1") (pintype "passive"))
      (node (ref "U9") (pin "25") (pinfunction "GPIO5/I2S_MCLK_25") (pintype "bidirectional"))
    )
    (net (code "57") (name "Net-(U9A-GPIO6{slash}I2S_SCLK)") (class "Default")
      (node (ref "R25") (pin "6") (pinfunction "6_6") (pintype "passive"))
      (node (ref "U9") (pin "11") (pinfunction "GPIO6/I2S_SCLK_11") (pintype "bidirectional"))
    )
    (net (code "58") (name "Net-(U9A-GPIO7{slash}I2S_DATA)") (class "Default")
      (node (ref "R25") (pin "8") (pinfunction "8_8") (pintype "passive"))
      (node (ref "U9") (pin "12") (pinfunction "GPIO7/I2S_DATA_12") (pintype "bidirectional"))
    )
    (net (code "59") (name "Net-(U9A-TEST)") (class "Default")
      (node (ref "R14") (pin "2") (pinfunction "2_2") (pintype "passive"))
      (node (ref "U9") (pin "32") (pinfunction "TEST_32") (pintype "input"))
    )
    (net (code "60") (name "Net-(U11-BP)") (class "Default")
      (node (ref "C27") (pin "1") (pinfunction "1_1") (pintype "passive"))
      (node (ref "U11") (pin "4") (pinfunction "BP_4") (pintype "input"))
    )
    (net (code "61") (name "Net-(U12-BP)") (class "Default")
      (node (ref "C30") (pin "1") (pinfunction "1_1") (pintype "passive"))
      (node (ref "U12") (pin "4") (pinfunction "BP_4") (pintype "input"))
    )
    (net (code "62") (name "unconnected-(JP2-Pad3)") (class "Default")
      (node (ref "JP2") (pin "3") (pinfunction "3_3") (pintype "passive"))
    )
    (net (code "63") (name "unconnected-(R16-Pad2)") (class "Default")
      (node (ref "R16") (pin "2") (pinfunction "2_2") (pintype "passive"))
    )
    (net (code "64") (name "unconnected-(S1-Pad1)") (class "Default")
      (node (ref "S1") (pin "1") (pinfunction "1_1") (pintype "passive"))
    )
    (net (code "65") (name "unconnected-(S2-Pad1)") (class "Default")
      (node (ref "S2") (pin "1") (pinfunction "1_1") (pintype "passive"))
    )
    (net (code "66") (name "unconnected-(S3-Pad1)") (class "Default")
      (node (ref "S3") (pin "1") (pinfunction "1_1") (pintype "passive"))
    )
    (net (code "67") (name "unconnected-(U1-ADC6-Pad19)") (class "Default")
      (node (ref "U1") (pin "19") (pinfunction "ADC6_19") (pintype "bidirectional"))
    )
    (net (code "68") (name "unconnected-(U1-ADC7-Pad22)") (class "Default")
      (node (ref "U1") (pin "22") (pinfunction "ADC7_22") (pintype "bidirectional"))
    )
    (net (code "69") (name "unconnected-(U1-PB1(OC1A)-Pad13)") (class "Default")
      (node (ref "U1") (pin "13") (pinfunction "PB1(OC1A)_13") (pintype "bidirectional"))
    )
    (net (code "70") (name "unconnected-(U1-PD3(INT1)-Pad1)") (class "Default")
      (node (ref "U1") (pin "1") (pinfunction "PD3(INT1)_1") (pintype "bidirectional"))
    )
    (net (code "71") (name "unconnected-(U1-PD4(XCK{slash}T0)-Pad2)") (class "Default")
      (node (ref "U1") (pin "2") (pinfunction "PD4(XCK/T0)_2") (pintype "bidirectional"))
    )
    (net (code "72") (name "unconnected-(U1-PD5(T1)-Pad9)") (class "Default")
      (node (ref "U1") (pin "9") (pinfunction "PD5(T1)_9") (pintype "bidirectional"))
    )
    (net (code "73") (name "unconnected-(U3-NC-Pad1)") (class "Default")
      (node (ref "U3") (pin "1") (pinfunction "NC_1") (pintype "bidirectional"))
    )
    (net (code "74") (name "unconnected-(U3-RSV-Pad8)") (class "Default")
      (node (ref "U3") (pin "8") (pinfunction "RSV_8") (pintype "bidirectional"))
    )
    (net (code "75") (name "unconnected-(U3-SHIELD-PadCD1)") (class "Default")
      (node (ref "U3") (pin "CD1") (pinfunction "SHIELD_CD1") (pintype "bidirectional"))
    )
    (net (code "76") (name "unconnected-(U3-SHIELD-PadCD2)") (class "Default")
      (node (ref "U3") (pin "CD2") (pinfunction "SHIELD_CD2") (pintype "bidirectional"))
    )
    (net (code "77") (name "unconnected-(U9A-LINEINR-Pad48)") (class "Default")
      (node (ref "U9") (pin "48") (pinfunction "LINEINR_48") (pintype "input"))
    )
    (net (code "78") (name "unconnected-(U9A-MICN-Pad2)") (class "Default")
      (node (ref "U9") (pin "2") (pinfunction "MICN_2") (pintype "input"))
    )
    (net (code "79") (name "unconnected-(U9A-MICP{slash}LINEINL-Pad1)") (class "Default")
      (node (ref "U9") (pin "1") (pinfunction "MICP/LINEINL_1") (pintype "input"))
    )
    (net (code "80") (name "unconnected-(U9A-VCO-Pad15)") (class "Default")
      (node (ref "U9") (pin "15") (pinfunction "VCO_15") (pintype "output"))
    )
    (net (code "81") (name "unconnected-(X1-PadD+)") (class "Default")
      (node (ref "X1") (pin "D+") (pinfunction "D+_D+") (pintype "bidirectional"))
    )
    (net (code "82") (name "unconnected-(X1-PadD-)") (class "Default")
      (node (ref "X1") (pin "D-") (pinfunction "D-_D-") (pintype "bidirectional"))
    )
  )
)
